# LEDs.net
KiCad netlist of a schematic drawn in Altium Designer
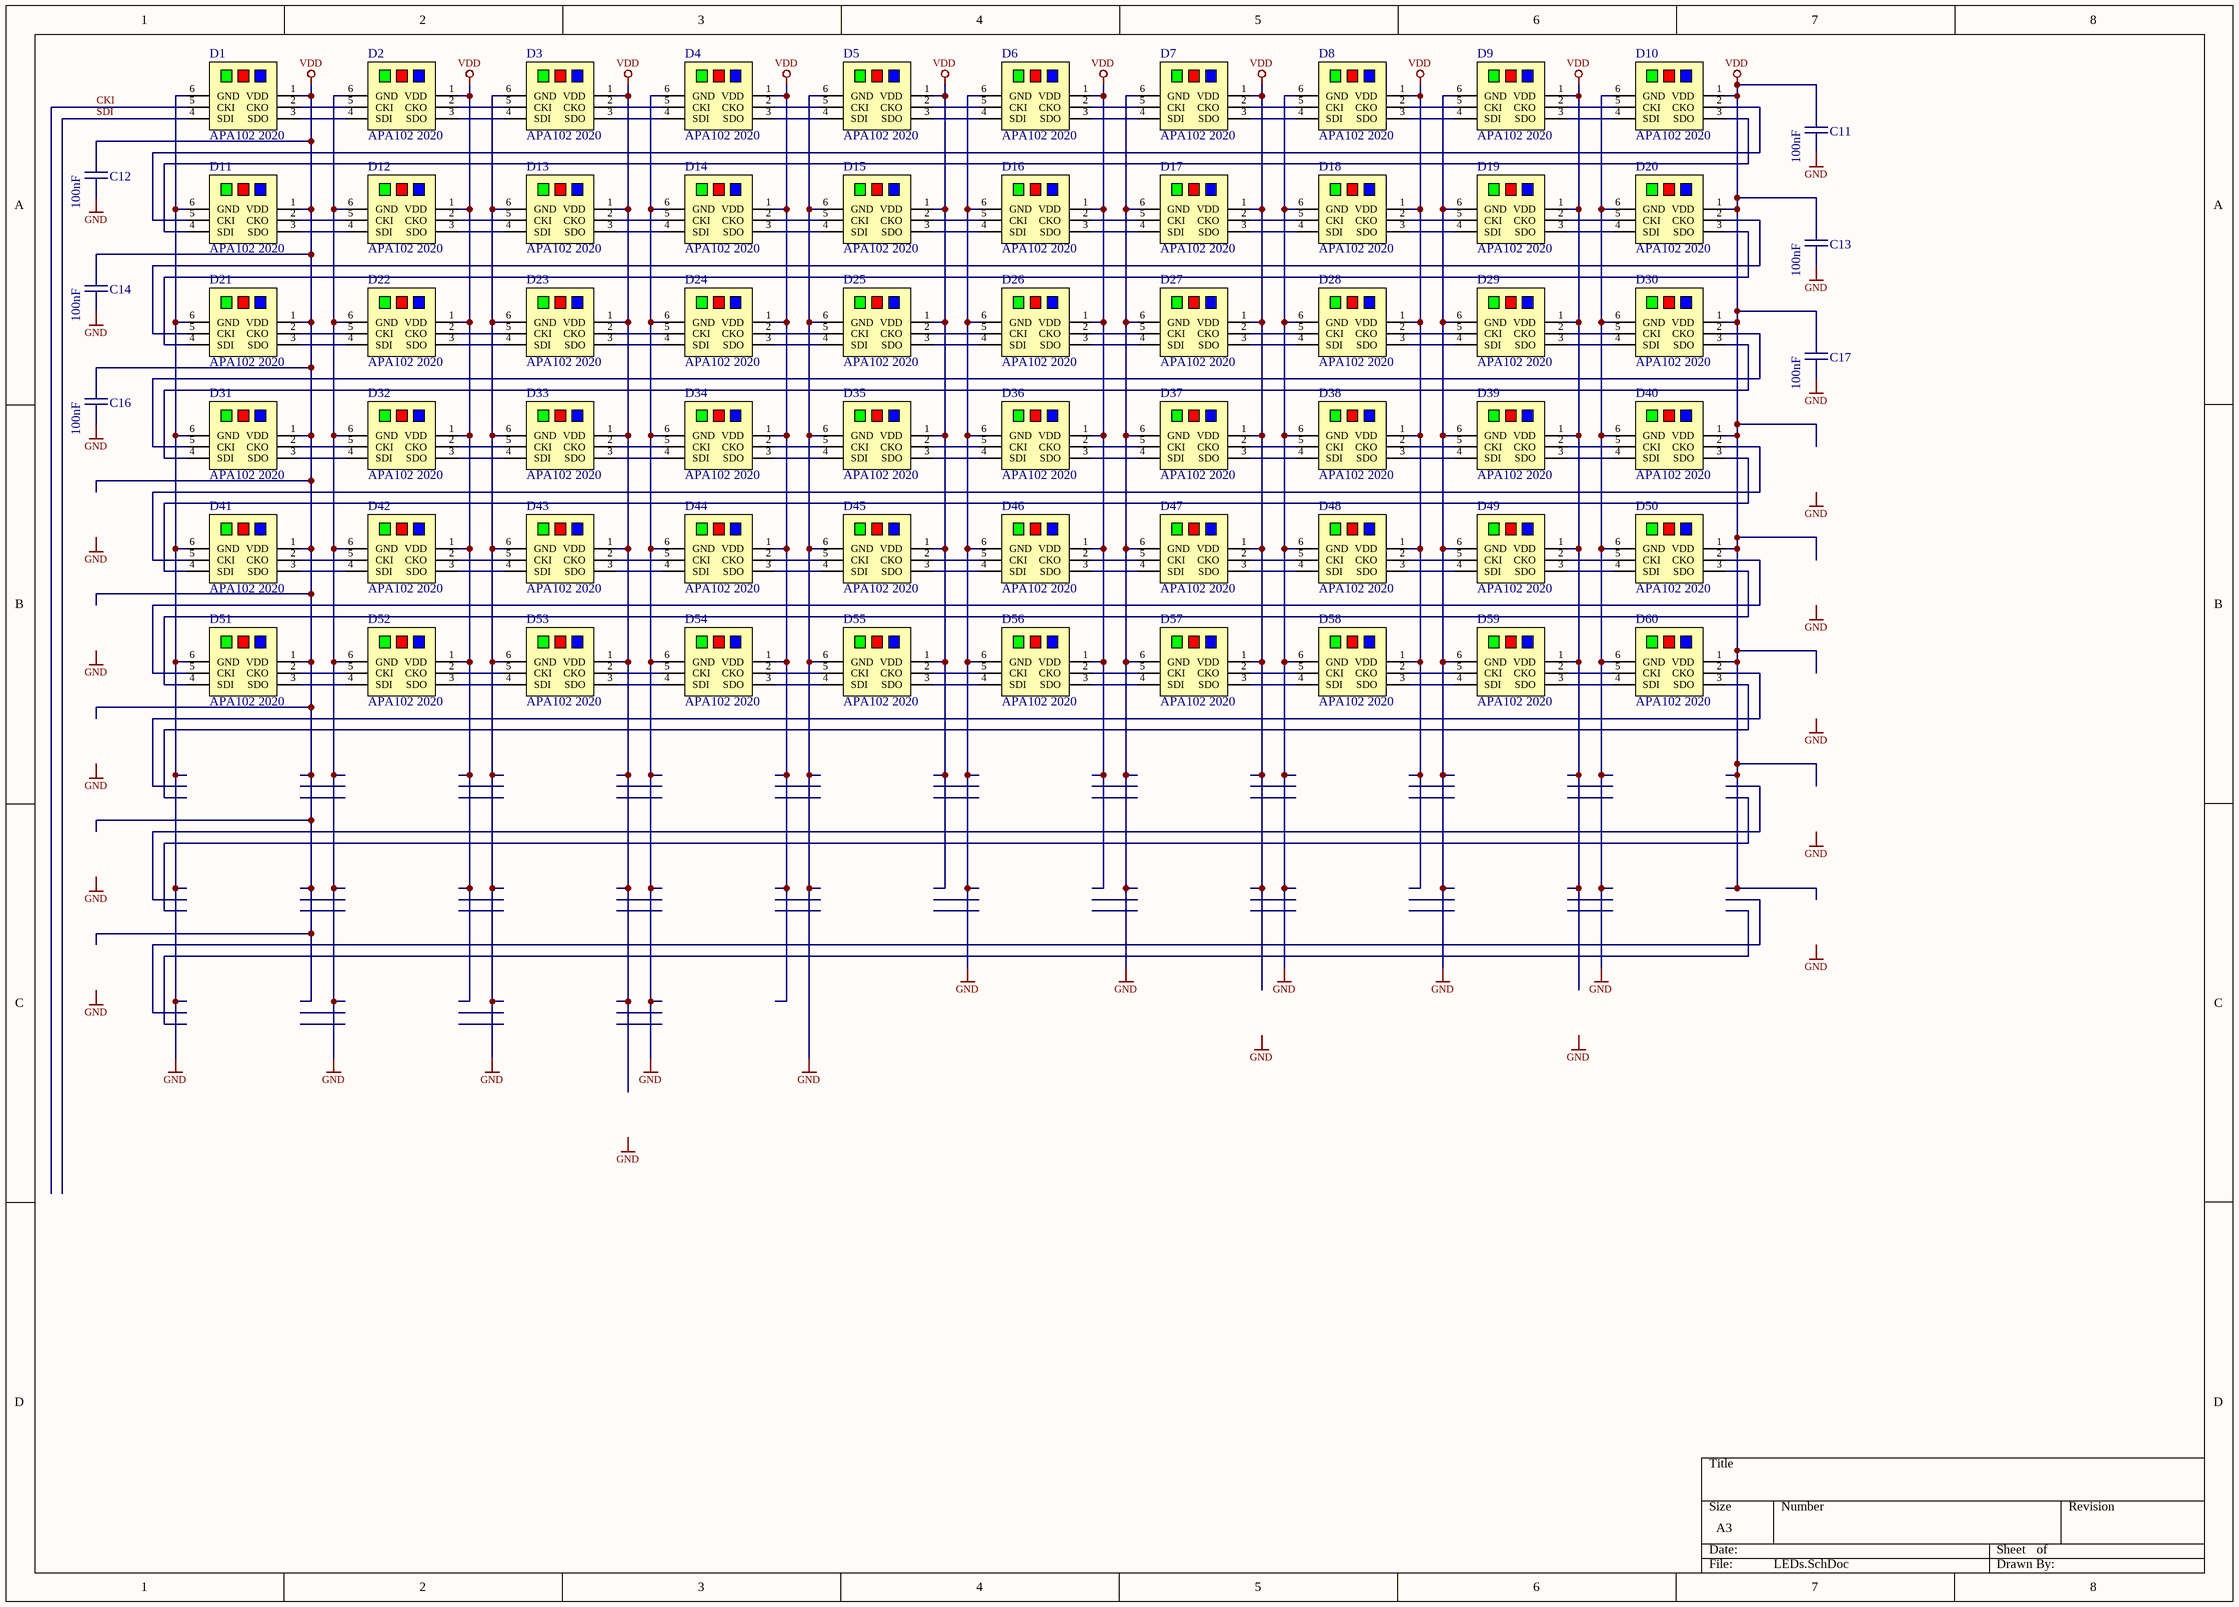
[diagram p0: LEDs.SchDoc]

(export (version "E")
  (design (tool "Eeschema 10.0.6"))
  (components
    (comp (ref "C11")
      (value "100nF")
      (footprint "CAPC0603(1608)55_N")
      (libsource (lib "OVLib_64") (part "CAP"))
    )
    (comp (ref "C12")
      (value "100nF")
      (footprint "CAPC0603(1608)55_N")
      (libsource (lib "OVLib_64") (part "CAP"))
    )
    (comp (ref "C13")
      (value "100nF")
      (footprint "CAPC0603(1608)55_N")
      (libsource (lib "OVLib_64") (part "CAP"))
    )
    (comp (ref "C14")
      (value "100nF")
      (footprint "CAPC0603(1608)55_N")
      (libsource (lib "OVLib_64") (part "CAP"))
    )
    (comp (ref "C16")
      (value "100nF")
      (footprint "CAPC0603(1608)55_N")
      (libsource (lib "OVLib_64") (part "CAP"))
    )
    (comp (ref "C17")
      (value "100nF")
      (footprint "CAPC0603(1608)55_N")
      (libsource (lib "OVLib_64") (part "CAP"))
    )
    (comp (ref "D1")
      (value "APA102 2020")
      (footprint "APA_RGB_LED_2020")
      (libsource (lib "OVLib_64") (part "LED_RGB_APA102"))
    )
    (comp (ref "D2")
      (value "APA102 2020")
      (footprint "APA_RGB_LED_2020")
      (libsource (lib "OVLib_64") (part "LED_RGB_APA102"))
    )
    (comp (ref "D3")
      (value "APA102 2020")
      (footprint "APA_RGB_LED_2020")
      (libsource (lib "OVLib_64") (part "LED_RGB_APA102"))
    )
    (comp (ref "D4")
      (value "APA102 2020")
      (footprint "APA_RGB_LED_2020")
      (libsource (lib "OVLib_64") (part "LED_RGB_APA102"))
    )
    (comp (ref "D5")
      (value "APA102 2020")
      (footprint "APA_RGB_LED_2020")
      (libsource (lib "OVLib_64") (part "LED_RGB_APA102"))
    )
    (comp (ref "D6")
      (value "APA102 2020")
      (footprint "APA_RGB_LED_2020")
      (libsource (lib "OVLib_64") (part "LED_RGB_APA102"))
    )
    (comp (ref "D7")
      (value "APA102 2020")
      (footprint "APA_RGB_LED_2020")
      (libsource (lib "OVLib_64") (part "LED_RGB_APA102"))
    )
    (comp (ref "D8")
      (value "APA102 2020")
      (footprint "APA_RGB_LED_2020")
      (libsource (lib "OVLib_64") (part "LED_RGB_APA102"))
    )
    (comp (ref "D9")
      (value "APA102 2020")
      (footprint "APA_RGB_LED_2020")
      (libsource (lib "OVLib_64") (part "LED_RGB_APA102"))
    )
    (comp (ref "D10")
      (value "APA102 2020")
      (footprint "APA_RGB_LED_2020")
      (libsource (lib "OVLib_64") (part "LED_RGB_APA102"))
    )
    (comp (ref "D11")
      (value "APA102 2020")
      (footprint "APA_RGB_LED_2020")
      (libsource (lib "OVLib_64") (part "LED_RGB_APA102"))
    )
    (comp (ref "D12")
      (value "APA102 2020")
      (footprint "APA_RGB_LED_2020")
      (libsource (lib "OVLib_64") (part "LED_RGB_APA102"))
    )
    (comp (ref "D13")
      (value "APA102 2020")
      (footprint "APA_RGB_LED_2020")
      (libsource (lib "OVLib_64") (part "LED_RGB_APA102"))
    )
    (comp (ref "D14")
      (value "APA102 2020")
      (footprint "APA_RGB_LED_2020")
      (libsource (lib "OVLib_64") (part "LED_RGB_APA102"))
    )
    (comp (ref "D15")
      (value "APA102 2020")
      (footprint "APA_RGB_LED_2020")
      (libsource (lib "OVLib_64") (part "LED_RGB_APA102"))
    )
    (comp (ref "D16")
      (value "APA102 2020")
      (footprint "APA_RGB_LED_2020")
      (libsource (lib "OVLib_64") (part "LED_RGB_APA102"))
    )
    (comp (ref "D17")
      (value "APA102 2020")
      (footprint "APA_RGB_LED_2020")
      (libsource (lib "OVLib_64") (part "LED_RGB_APA102"))
    )
    (comp (ref "D18")
      (value "APA102 2020")
      (footprint "APA_RGB_LED_2020")
      (libsource (lib "OVLib_64") (part "LED_RGB_APA102"))
    )
    (comp (ref "D19")
      (value "APA102 2020")
      (footprint "APA_RGB_LED_2020")
      (libsource (lib "OVLib_64") (part "LED_RGB_APA102"))
    )
    (comp (ref "D20")
      (value "APA102 2020")
      (footprint "APA_RGB_LED_2020")
      (libsource (lib "OVLib_64") (part "LED_RGB_APA102"))
    )
    (comp (ref "D21")
      (value "APA102 2020")
      (footprint "APA_RGB_LED_2020")
      (libsource (lib "OVLib_64") (part "LED_RGB_APA102"))
    )
    (comp (ref "D22")
      (value "APA102 2020")
      (footprint "APA_RGB_LED_2020")
      (libsource (lib "OVLib_64") (part "LED_RGB_APA102"))
    )
    (comp (ref "D23")
      (value "APA102 2020")
      (footprint "APA_RGB_LED_2020")
      (libsource (lib "OVLib_64") (part "LED_RGB_APA102"))
    )
    (comp (ref "D24")
      (value "APA102 2020")
      (footprint "APA_RGB_LED_2020")
      (libsource (lib "OVLib_64") (part "LED_RGB_APA102"))
    )
    (comp (ref "D25")
      (value "APA102 2020")
      (footprint "APA_RGB_LED_2020")
      (libsource (lib "OVLib_64") (part "LED_RGB_APA102"))
    )
    (comp (ref "D26")
      (value "APA102 2020")
      (footprint "APA_RGB_LED_2020")
      (libsource (lib "OVLib_64") (part "LED_RGB_APA102"))
    )
    (comp (ref "D27")
      (value "APA102 2020")
      (footprint "APA_RGB_LED_2020")
      (libsource (lib "OVLib_64") (part "LED_RGB_APA102"))
    )
    (comp (ref "D28")
      (value "APA102 2020")
      (footprint "APA_RGB_LED_2020")
      (libsource (lib "OVLib_64") (part "LED_RGB_APA102"))
    )
    (comp (ref "D29")
      (value "APA102 2020")
      (footprint "APA_RGB_LED_2020")
      (libsource (lib "OVLib_64") (part "LED_RGB_APA102"))
    )
    (comp (ref "D30")
      (value "APA102 2020")
      (footprint "APA_RGB_LED_2020")
      (libsource (lib "OVLib_64") (part "LED_RGB_APA102"))
    )
    (comp (ref "D31")
      (value "APA102 2020")
      (footprint "APA_RGB_LED_2020")
      (libsource (lib "OVLib_64") (part "LED_RGB_APA102"))
    )
    (comp (ref "D32")
      (value "APA102 2020")
      (footprint "APA_RGB_LED_2020")
      (libsource (lib "OVLib_64") (part "LED_RGB_APA102"))
    )
    (comp (ref "D33")
      (value "APA102 2020")
      (footprint "APA_RGB_LED_2020")
      (libsource (lib "OVLib_64") (part "LED_RGB_APA102"))
    )
    (comp (ref "D34")
      (value "APA102 2020")
      (footprint "APA_RGB_LED_2020")
      (libsource (lib "OVLib_64") (part "LED_RGB_APA102"))
    )
    (comp (ref "D35")
      (value "APA102 2020")
      (footprint "APA_RGB_LED_2020")
      (libsource (lib "OVLib_64") (part "LED_RGB_APA102"))
    )
    (comp (ref "D36")
      (value "APA102 2020")
      (footprint "APA_RGB_LED_2020")
      (libsource (lib "OVLib_64") (part "LED_RGB_APA102"))
    )
    (comp (ref "D37")
      (value "APA102 2020")
      (footprint "APA_RGB_LED_2020")
      (libsource (lib "OVLib_64") (part "LED_RGB_APA102"))
    )
    (comp (ref "D38")
      (value "APA102 2020")
      (footprint "APA_RGB_LED_2020")
      (libsource (lib "OVLib_64") (part "LED_RGB_APA102"))
    )
    (comp (ref "D39")
      (value "APA102 2020")
      (footprint "APA_RGB_LED_2020")
      (libsource (lib "OVLib_64") (part "LED_RGB_APA102"))
    )
    (comp (ref "D40")
      (value "APA102 2020")
      (footprint "APA_RGB_LED_2020")
      (libsource (lib "OVLib_64") (part "LED_RGB_APA102"))
    )
    (comp (ref "D41")
      (value "APA102 2020")
      (footprint "APA_RGB_LED_2020")
      (libsource (lib "OVLib_64") (part "LED_RGB_APA102"))
    )
    (comp (ref "D42")
      (value "APA102 2020")
      (footprint "APA_RGB_LED_2020")
      (libsource (lib "OVLib_64") (part "LED_RGB_APA102"))
    )
    (comp (ref "D43")
      (value "APA102 2020")
      (footprint "APA_RGB_LED_2020")
      (libsource (lib "OVLib_64") (part "LED_RGB_APA102"))
    )
    (comp (ref "D44")
      (value "APA102 2020")
      (footprint "APA_RGB_LED_2020")
      (libsource (lib "OVLib_64") (part "LED_RGB_APA102"))
    )
    (comp (ref "D45")
      (value "APA102 2020")
      (footprint "APA_RGB_LED_2020")
      (libsource (lib "OVLib_64") (part "LED_RGB_APA102"))
    )
    (comp (ref "D46")
      (value "APA102 2020")
      (footprint "APA_RGB_LED_2020")
      (libsource (lib "OVLib_64") (part "LED_RGB_APA102"))
    )
    (comp (ref "D47")
      (value "APA102 2020")
      (footprint "APA_RGB_LED_2020")
      (libsource (lib "OVLib_64") (part "LED_RGB_APA102"))
    )
    (comp (ref "D48")
      (value "APA102 2020")
      (footprint "APA_RGB_LED_2020")
      (libsource (lib "OVLib_64") (part "LED_RGB_APA102"))
    )
    (comp (ref "D49")
      (value "APA102 2020")
      (footprint "APA_RGB_LED_2020")
      (libsource (lib "OVLib_64") (part "LED_RGB_APA102"))
    )
    (comp (ref "D50")
      (value "APA102 2020")
      (footprint "APA_RGB_LED_2020")
      (libsource (lib "OVLib_64") (part "LED_RGB_APA102"))
    )
    (comp (ref "D51")
      (value "APA102 2020")
      (footprint "APA_RGB_LED_2020")
      (libsource (lib "OVLib_64") (part "LED_RGB_APA102"))
    )
    (comp (ref "D52")
      (value "APA102 2020")
      (footprint "APA_RGB_LED_2020")
      (libsource (lib "OVLib_64") (part "LED_RGB_APA102"))
    )
    (comp (ref "D53")
      (value "APA102 2020")
      (footprint "APA_RGB_LED_2020")
      (libsource (lib "OVLib_64") (part "LED_RGB_APA102"))
    )
    (comp (ref "D54")
      (value "APA102 2020")
      (footprint "APA_RGB_LED_2020")
      (libsource (lib "OVLib_64") (part "LED_RGB_APA102"))
    )
    (comp (ref "D55")
      (value "APA102 2020")
      (footprint "APA_RGB_LED_2020")
      (libsource (lib "OVLib_64") (part "LED_RGB_APA102"))
    )
    (comp (ref "D56")
      (value "APA102 2020")
      (footprint "APA_RGB_LED_2020")
      (libsource (lib "OVLib_64") (part "LED_RGB_APA102"))
    )
    (comp (ref "D57")
      (value "APA102 2020")
      (footprint "APA_RGB_LED_2020")
      (libsource (lib "OVLib_64") (part "LED_RGB_APA102"))
    )
    (comp (ref "D58")
      (value "APA102 2020")
      (footprint "APA_RGB_LED_2020")
      (libsource (lib "OVLib_64") (part "LED_RGB_APA102"))
    )
    (comp (ref "D59")
      (value "APA102 2020")
      (footprint "APA_RGB_LED_2020")
      (libsource (lib "OVLib_64") (part "LED_RGB_APA102"))
    )
    (comp (ref "D60")
      (value "APA102 2020")
      (footprint "APA_RGB_LED_2020")
      (libsource (lib "OVLib_64") (part "LED_RGB_APA102"))
    )
  )
  (nets
    (net (code "1") (name "/CKI") (class "Default")
      (node (ref "D1") (pin "5") (pinfunction "CKI_5") (pintype "passive"))
    )
    (net (code "2") (name "/SDI") (class "Default")
      (node (ref "D1") (pin "4") (pinfunction "SDI_4") (pintype "passive"))
    )
    (net (code "3") (name "GND") (class "Default")
      (node (ref "C11") (pin "1") (pinfunction "1_1") (pintype "passive"))
      (node (ref "C12") (pin "1") (pinfunction "1_1") (pintype "passive"))
      (node (ref "C13") (pin "1") (pinfunction "1_1") (pintype "passive"))
      (node (ref "C14") (pin "1") (pinfunction "1_1") (pintype "passive"))
      (node (ref "C16") (pin "1") (pinfunction "1_1") (pintype "passive"))
      (node (ref "C17") (pin "1") (pinfunction "1_1") (pintype "passive"))
      (node (ref "D1") (pin "6") (pinfunction "GND_6") (pintype "passive"))
      (node (ref "D10") (pin "6") (pinfunction "GND_6") (pintype "passive"))
      (node (ref "D11") (pin "6") (pinfunction "GND_6") (pintype "passive"))
      (node (ref "D12") (pin "6") (pinfunction "GND_6") (pintype "passive"))
      (node (ref "D13") (pin "6") (pinfunction "GND_6") (pintype "passive"))
      (node (ref "D14") (pin "6") (pinfunction "GND_6") (pintype "passive"))
      (node (ref "D15") (pin "6") (pinfunction "GND_6") (pintype "passive"))
      (node (ref "D16") (pin "6") (pinfunction "GND_6") (pintype "passive"))
      (node (ref "D17") (pin "6") (pinfunction "GND_6") (pintype "passive"))
      (node (ref "D18") (pin "6") (pinfunction "GND_6") (pintype "passive"))
      (node (ref "D19") (pin "6") (pinfunction "GND_6") (pintype "passive"))
      (node (ref "D2") (pin "6") (pinfunction "GND_6") (pintype "passive"))
      (node (ref "D20") (pin "6") (pinfunction "GND_6") (pintype "passive"))
      (node (ref "D21") (pin "6") (pinfunction "GND_6") (pintype "passive"))
      (node (ref "D22") (pin "6") (pinfunction "GND_6") (pintype "passive"))
      (node (ref "D23") (pin "6") (pinfunction "GND_6") (pintype "passive"))
      (node (ref "D24") (pin "6") (pinfunction "GND_6") (pintype "passive"))
      (node (ref "D25") (pin "6") (pinfunction "GND_6") (pintype "passive"))
      (node (ref "D26") (pin "6") (pinfunction "GND_6") (pintype "passive"))
      (node (ref "D27") (pin "6") (pinfunction "GND_6") (pintype "passive"))
      (node (ref "D28") (pin "6") (pinfunction "GND_6") (pintype "passive"))
      (node (ref "D29") (pin "6") (pinfunction "GND_6") (pintype "passive"))
      (node (ref "D3") (pin "6") (pinfunction "GND_6") (pintype "passive"))
      (node (ref "D30") (pin "6") (pinfunction "GND_6") (pintype "passive"))
      (node (ref "D31") (pin "6") (pinfunction "GND_6") (pintype "passive"))
      (node (ref "D32") (pin "6") (pinfunction "GND_6") (pintype "passive"))
      (node (ref "D33") (pin "6") (pinfunction "GND_6") (pintype "passive"))
      (node (ref "D34") (pin "6") (pinfunction "GND_6") (pintype "passive"))
      (node (ref "D35") (pin "6") (pinfunction "GND_6") (pintype "passive"))
      (node (ref "D36") (pin "6") (pinfunction "GND_6") (pintype "passive"))
      (node (ref "D37") (pin "6") (pinfunction "GND_6") (pintype "passive"))
      (node (ref "D38") (pin "6") (pinfunction "GND_6") (pintype "passive"))
      (node (ref "D39") (pin "6") (pinfunction "GND_6") (pintype "passive"))
      (node (ref "D4") (pin "6") (pinfunction "GND_6") (pintype "passive"))
      (node (ref "D40") (pin "6") (pinfunction "GND_6") (pintype "passive"))
      (node (ref "D41") (pin "6") (pinfunction "GND_6") (pintype "passive"))
      (node (ref "D42") (pin "6") (pinfunction "GND_6") (pintype "passive"))
      (node (ref "D43") (pin "6") (pinfunction "GND_6") (pintype "passive"))
      (node (ref "D44") (pin "6") (pinfunction "GND_6") (pintype "passive"))
      (node (ref "D45") (pin "6") (pinfunction "GND_6") (pintype "passive"))
      (node (ref "D46") (pin "6") (pinfunction "GND_6") (pintype "passive"))
      (node (ref "D47") (pin "6") (pinfunction "GND_6") (pintype "passive"))
      (node (ref "D48") (pin "6") (pinfunction "GND_6") (pintype "passive"))
      (node (ref "D49") (pin "6") (pinfunction "GND_6") (pintype "passive"))
      (node (ref "D5") (pin "6") (pinfunction "GND_6") (pintype "passive"))
      (node (ref "D50") (pin "6") (pinfunction "GND_6") (pintype "passive"))
      (node (ref "D51") (pin "6") (pinfunction "GND_6") (pintype "passive"))
      (node (ref "D52") (pin "6") (pinfunction "GND_6") (pintype "passive"))
      (node (ref "D53") (pin "6") (pinfunction "GND_6") (pintype "passive"))
      (node (ref "D54") (pin "6") (pinfunction "GND_6") (pintype "passive"))
      (node (ref "D55") (pin "6") (pinfunction "GND_6") (pintype "passive"))
      (node (ref "D56") (pin "6") (pinfunction "GND_6") (pintype "passive"))
      (node (ref "D57") (pin "6") (pinfunction "GND_6") (pintype "passive"))
      (node (ref "D58") (pin "6") (pinfunction "GND_6") (pintype "passive"))
      (node (ref "D59") (pin "6") (pinfunction "GND_6") (pintype "passive"))
      (node (ref "D6") (pin "6") (pinfunction "GND_6") (pintype "passive"))
      (node (ref "D60") (pin "6") (pinfunction "GND_6") (pintype "passive"))
      (node (ref "D7") (pin "6") (pinfunction "GND_6") (pintype "passive"))
      (node (ref "D8") (pin "6") (pinfunction "GND_6") (pintype "passive"))
      (node (ref "D9") (pin "6") (pinfunction "GND_6") (pintype "passive"))
    )
    (net (code "4") (name "Net-(D1-CKO)") (class "Default")
      (node (ref "D1") (pin "2") (pinfunction "CKO_2") (pintype "passive"))
      (node (ref "D2") (pin "5") (pinfunction "CKI_5") (pintype "passive"))
    )
    (net (code "5") (name "Net-(D1-SDO)") (class "Default")
      (node (ref "D1") (pin "3") (pinfunction "SDO_3") (pintype "passive"))
      (node (ref "D2") (pin "4") (pinfunction "SDI_4") (pintype "passive"))
    )
    (net (code "6") (name "Net-(D2-CKO)") (class "Default")
      (node (ref "D2") (pin "2") (pinfunction "CKO_2") (pintype "passive"))
      (node (ref "D3") (pin "5") (pinfunction "CKI_5") (pintype "passive"))
    )
    (net (code "7") (name "Net-(D2-SDO)") (class "Default")
      (node (ref "D2") (pin "3") (pinfunction "SDO_3") (pintype "passive"))
      (node (ref "D3") (pin "4") (pinfunction "SDI_4") (pintype "passive"))
    )
    (net (code "8") (name "Net-(D3-CKO)") (class "Default")
      (node (ref "D3") (pin "2") (pinfunction "CKO_2") (pintype "passive"))
      (node (ref "D4") (pin "5") (pinfunction "CKI_5") (pintype "passive"))
    )
    (net (code "9") (name "Net-(D3-SDO)") (class "Default")
      (node (ref "D3") (pin "3") (pinfunction "SDO_3") (pintype "passive"))
      (node (ref "D4") (pin "4") (pinfunction "SDI_4") (pintype "passive"))
    )
    (net (code "10") (name "Net-(D4-CKO)") (class "Default")
      (node (ref "D4") (pin "2") (pinfunction "CKO_2") (pintype "passive"))
      (node (ref "D5") (pin "5") (pinfunction "CKI_5") (pintype "passive"))
    )
    (net (code "11") (name "Net-(D4-SDO)") (class "Default")
      (node (ref "D4") (pin "3") (pinfunction "SDO_3") (pintype "passive"))
      (node (ref "D5") (pin "4") (pinfunction "SDI_4") (pintype "passive"))
    )
    (net (code "12") (name "Net-(D5-CKO)") (class "Default")
      (node (ref "D5") (pin "2") (pinfunction "CKO_2") (pintype "passive"))
      (node (ref "D6") (pin "5") (pinfunction "CKI_5") (pintype "passive"))
    )
    (net (code "13") (name "Net-(D5-SDO)") (class "Default")
      (node (ref "D5") (pin "3") (pinfunction "SDO_3") (pintype "passive"))
      (node (ref "D6") (pin "4") (pinfunction "SDI_4") (pintype "passive"))
    )
    (net (code "14") (name "Net-(D6-CKO)") (class "Default")
      (node (ref "D6") (pin "2") (pinfunction "CKO_2") (pintype "passive"))
      (node (ref "D7") (pin "5") (pinfunction "CKI_5") (pintype "passive"))
    )
    (net (code "15") (name "Net-(D6-SDO)") (class "Default")
      (node (ref "D6") (pin "3") (pinfunction "SDO_3") (pintype "passive"))
      (node (ref "D7") (pin "4") (pinfunction "SDI_4") (pintype "passive"))
    )
    (net (code "16") (name "Net-(D7-CKO)") (class "Default")
      (node (ref "D7") (pin "2") (pinfunction "CKO_2") (pintype "passive"))
      (node (ref "D8") (pin "5") (pinfunction "CKI_5") (pintype "passive"))
    )
    (net (code "17") (name "Net-(D7-SDO)") (class "Default")
      (node (ref "D7") (pin "3") (pinfunction "SDO_3") (pintype "passive"))
      (node (ref "D8") (pin "4") (pinfunction "SDI_4") (pintype "passive"))
    )
    (net (code "18") (name "Net-(D8-CKO)") (class "Default")
      (node (ref "D8") (pin "2") (pinfunction "CKO_2") (pintype "passive"))
      (node (ref "D9") (pin "5") (pinfunction "CKI_5") (pintype "passive"))
    )
    (net (code "19") (name "Net-(D8-SDO)") (class "Default")
      (node (ref "D8") (pin "3") (pinfunction "SDO_3") (pintype "passive"))
      (node (ref "D9") (pin "4") (pinfunction "SDI_4") (pintype "passive"))
    )
    (net (code "20") (name "Net-(D10-CKI)") (class "Default")
      (node (ref "D10") (pin "5") (pinfunction "CKI_5") (pintype "passive"))
      (node (ref "D9") (pin "2") (pinfunction "CKO_2") (pintype "passive"))
    )
    (net (code "21") (name "Net-(D10-CKO)") (class "Default")
      (node (ref "D10") (pin "2") (pinfunction "CKO_2") (pintype "passive"))
      (node (ref "D11") (pin "5") (pinfunction "CKI_5") (pintype "passive"))
    )
    (net (code "22") (name "Net-(D10-SDI)") (class "Default")
      (node (ref "D10") (pin "4") (pinfunction "SDI_4") (pintype "passive"))
      (node (ref "D9") (pin "3") (pinfunction "SDO_3") (pintype "passive"))
    )
    (net (code "23") (name "Net-(D10-SDO)") (class "Default")
      (node (ref "D10") (pin "3") (pinfunction "SDO_3") (pintype "passive"))
      (node (ref "D11") (pin "4") (pinfunction "SDI_4") (pintype "passive"))
    )
    (net (code "24") (name "Net-(D11-CKO)") (class "Default")
      (node (ref "D11") (pin "2") (pinfunction "CKO_2") (pintype "passive"))
      (node (ref "D12") (pin "5") (pinfunction "CKI_5") (pintype "passive"))
    )
    (net (code "25") (name "Net-(D11-SDO)") (class "Default")
      (node (ref "D11") (pin "3") (pinfunction "SDO_3") (pintype "passive"))
      (node (ref "D12") (pin "4") (pinfunction "SDI_4") (pintype "passive"))
    )
    (net (code "26") (name "Net-(D12-CKO)") (class "Default")
      (node (ref "D12") (pin "2") (pinfunction "CKO_2") (pintype "passive"))
      (node (ref "D13") (pin "5") (pinfunction "CKI_5") (pintype "passive"))
    )
    (net (code "27") (name "Net-(D12-SDO)") (class "Default")
      (node (ref "D12") (pin "3") (pinfunction "SDO_3") (pintype "passive"))
      (node (ref "D13") (pin "4") (pinfunction "SDI_4") (pintype "passive"))
    )
    (net (code "28") (name "Net-(D13-CKO)") (class "Default")
      (node (ref "D13") (pin "2") (pinfunction "CKO_2") (pintype "passive"))
      (node (ref "D14") (pin "5") (pinfunction "CKI_5") (pintype "passive"))
    )
    (net (code "29") (name "Net-(D13-SDO)") (class "Default")
      (node (ref "D13") (pin "3") (pinfunction "SDO_3") (pintype "passive"))
      (node (ref "D14") (pin "4") (pinfunction "SDI_4") (pintype "passive"))
    )
    (net (code "30") (name "Net-(D14-CKO)") (class "Default")
      (node (ref "D14") (pin "2") (pinfunction "CKO_2") (pintype "passive"))
      (node (ref "D15") (pin "5") (pinfunction "CKI_5") (pintype "passive"))
    )
    (net (code "31") (name "Net-(D14-SDO)") (class "Default")
      (node (ref "D14") (pin "3") (pinfunction "SDO_3") (pintype "passive"))
      (node (ref "D15") (pin "4") (pinfunction "SDI_4") (pintype "passive"))
    )
    (net (code "32") (name "Net-(D15-CKO)") (class "Default")
      (node (ref "D15") (pin "2") (pinfunction "CKO_2") (pintype "passive"))
      (node (ref "D16") (pin "5") (pinfunction "CKI_5") (pintype "passive"))
    )
    (net (code "33") (name "Net-(D15-SDO)") (class "Default")
      (node (ref "D15") (pin "3") (pinfunction "SDO_3") (pintype "passive"))
      (node (ref "D16") (pin "4") (pinfunction "SDI_4") (pintype "passive"))
    )
    (net (code "34") (name "Net-(D16-CKO)") (class "Default")
      (node (ref "D16") (pin "2") (pinfunction "CKO_2") (pintype "passive"))
      (node (ref "D17") (pin "5") (pinfunction "CKI_5") (pintype "passive"))
    )
    (net (code "35") (name "Net-(D16-SDO)") (class "Default")
      (node (ref "D16") (pin "3") (pinfunction "SDO_3") (pintype "passive"))
      (node (ref "D17") (pin "4") (pinfunction "SDI_4") (pintype "passive"))
    )
    (net (code "36") (name "Net-(D17-CKO)") (class "Default")
      (node (ref "D17") (pin "2") (pinfunction "CKO_2") (pintype "passive"))
      (node (ref "D18") (pin "5") (pinfunction "CKI_5") (pintype "passive"))
    )
    (net (code "37") (name "Net-(D17-SDO)") (class "Default")
      (node (ref "D17") (pin "3") (pinfunction "SDO_3") (pintype "passive"))
      (node (ref "D18") (pin "4") (pinfunction "SDI_4") (pintype "passive"))
    )
    (net (code "38") (name "Net-(D18-CKO)") (class "Default")
      (node (ref "D18") (pin "2") (pinfunction "CKO_2") (pintype "passive"))
      (node (ref "D19") (pin "5") (pinfunction "CKI_5") (pintype "passive"))
    )
    (net (code "39") (name "Net-(D18-SDO)") (class "Default")
      (node (ref "D18") (pin "3") (pinfunction "SDO_3") (pintype "passive"))
      (node (ref "D19") (pin "4") (pinfunction "SDI_4") (pintype "passive"))
    )
    (net (code "40") (name "Net-(D19-CKO)") (class "Default")
      (node (ref "D19") (pin "2") (pinfunction "CKO_2") (pintype "passive"))
      (node (ref "D20") (pin "5") (pinfunction "CKI_5") (pintype "passive"))
    )
    (net (code "41") (name "Net-(D19-SDO)") (class "Default")
      (node (ref "D19") (pin "3") (pinfunction "SDO_3") (pintype "passive"))
      (node (ref "D20") (pin "4") (pinfunction "SDI_4") (pintype "passive"))
    )
    (net (code "42") (name "Net-(D20-CKO)") (class "Default")
      (node (ref "D20") (pin "2") (pinfunction "CKO_2") (pintype "passive"))
      (node (ref "D21") (pin "5") (pinfunction "CKI_5") (pintype "passive"))
    )
    (net (code "43") (name "Net-(D20-SDO)") (class "Default")
      (node (ref "D20") (pin "3") (pinfunction "SDO_3") (pintype "passive"))
      (node (ref "D21") (pin "4") (pinfunction "SDI_4") (pintype "passive"))
    )
    (net (code "44") (name "Net-(D21-CKO)") (class "Default")
      (node (ref "D21") (pin "2") (pinfunction "CKO_2") (pintype "passive"))
      (node (ref "D22") (pin "5") (pinfunction "CKI_5") (pintype "passive"))
    )
    (net (code "45") (name "Net-(D21-SDO)") (class "Default")
      (node (ref "D21") (pin "3") (pinfunction "SDO_3") (pintype "passive"))
      (node (ref "D22") (pin "4") (pinfunction "SDI_4") (pintype "passive"))
    )
    (net (code "46") (name "Net-(D22-CKO)") (class "Default")
      (node (ref "D22") (pin "2") (pinfunction "CKO_2") (pintype "passive"))
      (node (ref "D23") (pin "5") (pinfunction "CKI_5") (pintype "passive"))
    )
    (net (code "47") (name "Net-(D22-SDO)") (class "Default")
      (node (ref "D22") (pin "3") (pinfunction "SDO_3") (pintype "passive"))
      (node (ref "D23") (pin "4") (pinfunction "SDI_4") (pintype "passive"))
    )
    (net (code "48") (name "Net-(D23-CKO)") (class "Default")
      (node (ref "D23") (pin "2") (pinfunction "CKO_2") (pintype "passive"))
      (node (ref "D24") (pin "5") (pinfunction "CKI_5") (pintype "passive"))
    )
    (net (code "49") (name "Net-(D23-SDO)") (class "Default")
      (node (ref "D23") (pin "3") (pinfunction "SDO_3") (pintype "passive"))
      (node (ref "D24") (pin "4") (pinfunction "SDI_4") (pintype "passive"))
    )
    (net (code "50") (name "Net-(D24-CKO)") (class "Default")
      (node (ref "D24") (pin "2") (pinfunction "CKO_2") (pintype "passive"))
      (node (ref "D25") (pin "5") (pinfunction "CKI_5") (pintype "passive"))
    )
    (net (code "51") (name "Net-(D24-SDO)") (class "Default")
      (node (ref "D24") (pin "3") (pinfunction "SDO_3") (pintype "passive"))
      (node (ref "D25") (pin "4") (pinfunction "SDI_4") (pintype "passive"))
    )
    (net (code "52") (name "Net-(D25-CKO)") (class "Default")
      (node (ref "D25") (pin "2") (pinfunction "CKO_2") (pintype "passive"))
      (node (ref "D26") (pin "5") (pinfunction "CKI_5") (pintype "passive"))
    )
    (net (code "53") (name "Net-(D25-SDO)") (class "Default")
      (node (ref "D25") (pin "3") (pinfunction "SDO_3") (pintype "passive"))
      (node (ref "D26") (pin "4") (pinfunction "SDI_4") (pintype "passive"))
    )
    (net (code "54") (name "Net-(D26-CKO)") (class "Default")
      (node (ref "D26") (pin "2") (pinfunction "CKO_2") (pintype "passive"))
      (node (ref "D27") (pin "5") (pinfunction "CKI_5") (pintype "passive"))
    )
    (net (code "55") (name "Net-(D26-SDO)") (class "Default")
      (node (ref "D26") (pin "3") (pinfunction "SDO_3") (pintype "passive"))
      (node (ref "D27") (pin "4") (pinfunction "SDI_4") (pintype "passive"))
    )
    (net (code "56") (name "Net-(D27-CKO)") (class "Default")
      (node (ref "D27") (pin "2") (pinfunction "CKO_2") (pintype "passive"))
      (node (ref "D28") (pin "5") (pinfunction "CKI_5") (pintype "passive"))
    )
    (net (code "57") (name "Net-(D27-SDO)") (class "Default")
      (node (ref "D27") (pin "3") (pinfunction "SDO_3") (pintype "passive"))
      (node (ref "D28") (pin "4") (pinfunction "SDI_4") (pintype "passive"))
    )
    (net (code "58") (name "Net-(D28-CKO)") (class "Default")
      (node (ref "D28") (pin "2") (pinfunction "CKO_2") (pintype "passive"))
      (node (ref "D29") (pin "5") (pinfunction "CKI_5") (pintype "passive"))
    )
    (net (code "59") (name "Net-(D28-SDO)") (class "Default")
      (node (ref "D28") (pin "3") (pinfunction "SDO_3") (pintype "passive"))
      (node (ref "D29") (pin "4") (pinfunction "SDI_4") (pintype "passive"))
    )
    (net (code "60") (name "Net-(D29-CKO)") (class "Default")
      (node (ref "D29") (pin "2") (pinfunction "CKO_2") (pintype "passive"))
      (node (ref "D30") (pin "5") (pinfunction "CKI_5") (pintype "passive"))
    )
    (net (code "61") (name "Net-(D29-SDO)") (class "Default")
      (node (ref "D29") (pin "3") (pinfunction "SDO_3") (pintype "passive"))
      (node (ref "D30") (pin "4") (pinfunction "SDI_4") (pintype "passive"))
    )
    (net (code "62") (name "Net-(D30-CKO)") (class "Default")
      (node (ref "D30") (pin "2") (pinfunction "CKO_2") (pintype "passive"))
      (node (ref "D31") (pin "5") (pinfunction "CKI_5") (pintype "passive"))
    )
    (net (code "63") (name "Net-(D30-SDO)") (class "Default")
      (node (ref "D30") (pin "3") (pinfunction "SDO_3") (pintype "passive"))
      (node (ref "D31") (pin "4") (pinfunction "SDI_4") (pintype "passive"))
    )
    (net (code "64") (name "Net-(D31-CKO)") (class "Default")
      (node (ref "D31") (pin "2") (pinfunction "CKO_2") (pintype "passive"))
      (node (ref "D32") (pin "5") (pinfunction "CKI_5") (pintype "passive"))
    )
    (net (code "65") (name "Net-(D31-SDO)") (class "Default")
      (node (ref "D31") (pin "3") (pinfunction "SDO_3") (pintype "passive"))
      (node (ref "D32") (pin "4") (pinfunction "SDI_4") (pintype "passive"))
    )
    (net (code "66") (name "Net-(D32-CKO)") (class "Default")
      (node (ref "D32") (pin "2") (pinfunction "CKO_2") (pintype "passive"))
      (node (ref "D33") (pin "5") (pinfunction "CKI_5") (pintype "passive"))
    )
    (net (code "67") (name "Net-(D32-SDO)") (class "Default")
      (node (ref "D32") (pin "3") (pinfunction "SDO_3") (pintype "passive"))
      (node (ref "D33") (pin "4") (pinfunction "SDI_4") (pintype "passive"))
    )
    (net (code "68") (name "Net-(D33-CKO)") (class "Default")
      (node (ref "D33") (pin "2") (pinfunction "CKO_2") (pintype "passive"))
      (node (ref "D34") (pin "5") (pinfunction "CKI_5") (pintype "passive"))
    )
    (net (code "69") (name "Net-(D33-SDO)") (class "Default")
      (node (ref "D33") (pin "3") (pinfunction "SDO_3") (pintype "passive"))
      (node (ref "D34") (pin "4") (pinfunction "SDI_4") (pintype "passive"))
    )
    (net (code "70") (name "Net-(D34-CKO)") (class "Default")
      (node (ref "D34") (pin "2") (pinfunction "CKO_2") (pintype "passive"))
      (node (ref "D35") (pin "5") (pinfunction "CKI_5") (pintype "passive"))
    )
    (net (code "71") (name "Net-(D34-SDO)") (class "Default")
      (node (ref "D34") (pin "3") (pinfunction "SDO_3") (pintype "passive"))
      (node (ref "D35") (pin "4") (pinfunction "SDI_4") (pintype "passive"))
    )
    (net (code "72") (name "Net-(D35-CKO)") (class "Default")
      (node (ref "D35") (pin "2") (pinfunction "CKO_2") (pintype "passive"))
      (node (ref "D36") (pin "5") (pinfunction "CKI_5") (pintype "passive"))
    )
    (net (code "73") (name "Net-(D35-SDO)") (class "Default")
      (node (ref "D35") (pin "3") (pinfunction "SDO_3") (pintype "passive"))
      (node (ref "D36") (pin "4") (pinfunction "SDI_4") (pintype "passive"))
    )
    (net (code "74") (name "Net-(D36-CKO)") (class "Default")
      (node (ref "D36") (pin "2") (pinfunction "CKO_2") (pintype "passive"))
      (node (ref "D37") (pin "5") (pinfunction "CKI_5") (pintype "passive"))
    )
    (net (code "75") (name "Net-(D36-SDO)") (class "Default")
      (node (ref "D36") (pin "3") (pinfunction "SDO_3") (pintype "passive"))
      (node (ref "D37") (pin "4") (pinfunction "SDI_4") (pintype "passive"))
    )
    (net (code "76") (name "Net-(D37-CKO)") (class "Default")
      (node (ref "D37") (pin "2") (pinfunction "CKO_2") (pintype "passive"))
      (node (ref "D38") (pin "5") (pinfunction "CKI_5") (pintype "passive"))
    )
    (net (code "77") (name "Net-(D37-SDO)") (class "Default")
      (node (ref "D37") (pin "3") (pinfunction "SDO_3") (pintype "passive"))
      (node (ref "D38") (pin "4") (pinfunction "SDI_4") (pintype "passive"))
    )
    (net (code "78") (name "Net-(D38-CKO)") (class "Default")
      (node (ref "D38") (pin "2") (pinfunction "CKO_2") (pintype "passive"))
      (node (ref "D39") (pin "5") (pinfunction "CKI_5") (pintype "passive"))
    )
    (net (code "79") (name "Net-(D38-SDO)") (class "Default")
      (node (ref "D38") (pin "3") (pinfunction "SDO_3") (pintype "passive"))
      (node (ref "D39") (pin "4") (pinfunction "SDI_4") (pintype "passive"))
    )
    (net (code "80") (name "Net-(D39-CKO)") (class "Default")
      (node (ref "D39") (pin "2") (pinfunction "CKO_2") (pintype "passive"))
      (node (ref "D40") (pin "5") (pinfunction "CKI_5") (pintype "passive"))
    )
    (net (code "81") (name "Net-(D39-SDO)") (class "Default")
      (node (ref "D39") (pin "3") (pinfunction "SDO_3") (pintype "passive"))
      (node (ref "D40") (pin "4") (pinfunction "SDI_4") (pintype "passive"))
    )
    (net (code "82") (name "Net-(D40-CKO)") (class "Default")
      (node (ref "D40") (pin "2") (pinfunction "CKO_2") (pintype "passive"))
      (node (ref "D41") (pin "5") (pinfunction "CKI_5") (pintype "passive"))
    )
    (net (code "83") (name "Net-(D40-SDO)") (class "Default")
      (node (ref "D40") (pin "3") (pinfunction "SDO_3") (pintype "passive"))
      (node (ref "D41") (pin "4") (pinfunction "SDI_4") (pintype "passive"))
    )
    (net (code "84") (name "Net-(D41-CKO)") (class "Default")
      (node (ref "D41") (pin "2") (pinfunction "CKO_2") (pintype "passive"))
      (node (ref "D42") (pin "5") (pinfunction "CKI_5") (pintype "passive"))
    )
    (net (code "85") (name "Net-(D41-SDO)") (class "Default")
      (node (ref "D41") (pin "3") (pinfunction "SDO_3") (pintype "passive"))
      (node (ref "D42") (pin "4") (pinfunction "SDI_4") (pintype "passive"))
    )
    (net (code "86") (name "Net-(D42-CKO)") (class "Default")
      (node (ref "D42") (pin "2") (pinfunction "CKO_2") (pintype "passive"))
      (node (ref "D43") (pin "5") (pinfunction "CKI_5") (pintype "passive"))
    )
    (net (code "87") (name "Net-(D42-SDO)") (class "Default")
      (node (ref "D42") (pin "3") (pinfunction "SDO_3") (pintype "passive"))
      (node (ref "D43") (pin "4") (pinfunction "SDI_4") (pintype "passive"))
    )
    (net (code "88") (name "Net-(D43-CKO)") (class "Default")
      (node (ref "D43") (pin "2") (pinfunction "CKO_2") (pintype "passive"))
      (node (ref "D44") (pin "5") (pinfunction "CKI_5") (pintype "passive"))
    )
    (net (code "89") (name "Net-(D43-SDO)") (class "Default")
      (node (ref "D43") (pin "3") (pinfunction "SDO_3") (pintype "passive"))
      (node (ref "D44") (pin "4") (pinfunction "SDI_4") (pintype "passive"))
    )
    (net (code "90") (name "Net-(D44-CKO)") (class "Default")
      (node (ref "D44") (pin "2") (pinfunction "CKO_2") (pintype "passive"))
      (node (ref "D45") (pin "5") (pinfunction "CKI_5") (pintype "passive"))
    )
    (net (code "91") (name "Net-(D44-SDO)") (class "Default")
      (node (ref "D44") (pin "3") (pinfunction "SDO_3") (pintype "passive"))
      (node (ref "D45") (pin "4") (pinfunction "SDI_4") (pintype "passive"))
    )
    (net (code "92") (name "Net-(D45-CKO)") (class "Default")
      (node (ref "D45") (pin "2") (pinfunction "CKO_2") (pintype "passive"))
      (node (ref "D46") (pin "5") (pinfunction "CKI_5") (pintype "passive"))
    )
    (net (code "93") (name "Net-(D45-SDO)") (class "Default")
      (node (ref "D45") (pin "3") (pinfunction "SDO_3") (pintype "passive"))
      (node (ref "D46") (pin "4") (pinfunction "SDI_4") (pintype "passive"))
    )
    (net (code "94") (name "Net-(D46-CKO)") (class "Default")
      (node (ref "D46") (pin "2") (pinfunction "CKO_2") (pintype "passive"))
      (node (ref "D47") (pin "5") (pinfunction "CKI_5") (pintype "passive"))
    )
    (net (code "95") (name "Net-(D46-SDO)") (class "Default")
      (node (ref "D46") (pin "3") (pinfunction "SDO_3") (pintype "passive"))
      (node (ref "D47") (pin "4") (pinfunction "SDI_4") (pintype "passive"))
    )
    (net (code "96") (name "Net-(D47-CKO)") (class "Default")
      (node (ref "D47") (pin "2") (pinfunction "CKO_2") (pintype "passive"))
      (node (ref "D48") (pin "5") (pinfunction "CKI_5") (pintype "passive"))
    )
    (net (code "97") (name "Net-(D47-SDO)") (class "Default")
      (node (ref "D47") (pin "3") (pinfunction "SDO_3") (pintype "passive"))
      (node (ref "D48") (pin "4") (pinfunction "SDI_4") (pintype "passive"))
    )
    (net (code "98") (name "Net-(D48-CKO)") (class "Default")
      (node (ref "D48") (pin "2") (pinfunction "CKO_2") (pintype "passive"))
      (node (ref "D49") (pin "5") (pinfunction "CKI_5") (pintype "passive"))
    )
    (net (code "99") (name "Net-(D48-SDO)") (class "Default")
      (node (ref "D48") (pin "3") (pinfunction "SDO_3") (pintype "passive"))
      (node (ref "D49") (pin "4") (pinfunction "SDI_4") (pintype "passive"))
    )
    (net (code "100") (name "Net-(D49-CKO)") (class "Default")
      (node (ref "D49") (pin "2") (pinfunction "CKO_2") (pintype "passive"))
      (node (ref "D50") (pin "5") (pinfunction "CKI_5") (pintype "passive"))
    )
    (net (code "101") (name "Net-(D49-SDO)") (class "Default")
      (node (ref "D49") (pin "3") (pinfunction "SDO_3") (pintype "passive"))
      (node (ref "D50") (pin "4") (pinfunction "SDI_4") (pintype "passive"))
    )
    (net (code "102") (name "Net-(D50-CKO)") (class "Default")
      (node (ref "D50") (pin "2") (pinfunction "CKO_2") (pintype "passive"))
      (node (ref "D51") (pin "5") (pinfunction "CKI_5") (pintype "passive"))
    )
    (net (code "103") (name "Net-(D50-SDO)") (class "Default")
      (node (ref "D50") (pin "3") (pinfunction "SDO_3") (pintype "passive"))
      (node (ref "D51") (pin "4") (pinfunction "SDI_4") (pintype "passive"))
    )
    (net (code "104") (name "Net-(D51-CKO)") (class "Default")
      (node (ref "D51") (pin "2") (pinfunction "CKO_2") (pintype "passive"))
      (node (ref "D52") (pin "5") (pinfunction "CKI_5") (pintype "passive"))
    )
    (net (code "105") (name "Net-(D51-SDO)") (class "Default")
      (node (ref "D51") (pin "3") (pinfunction "SDO_3") (pintype "passive"))
      (node (ref "D52") (pin "4") (pinfunction "SDI_4") (pintype "passive"))
    )
    (net (code "106") (name "Net-(D52-CKO)") (class "Default")
      (node (ref "D52") (pin "2") (pinfunction "CKO_2") (pintype "passive"))
      (node (ref "D53") (pin "5") (pinfunction "CKI_5") (pintype "passive"))
    )
    (net (code "107") (name "Net-(D52-SDO)") (class "Default")
      (node (ref "D52") (pin "3") (pinfunction "SDO_3") (pintype "passive"))
      (node (ref "D53") (pin "4") (pinfunction "SDI_4") (pintype "passive"))
    )
    (net (code "108") (name "Net-(D53-CKO)") (class "Default")
      (node (ref "D53") (pin "2") (pinfunction "CKO_2") (pintype "passive"))
      (node (ref "D54") (pin "5") (pinfunction "CKI_5") (pintype "passive"))
    )
    (net (code "109") (name "Net-(D53-SDO)") (class "Default")
      (node (ref "D53") (pin "3") (pinfunction "SDO_3") (pintype "passive"))
      (node (ref "D54") (pin "4") (pinfunction "SDI_4") (pintype "passive"))
    )
    (net (code "110") (name "Net-(D54-CKO)") (class "Default")
      (node (ref "D54") (pin "2") (pinfunction "CKO_2") (pintype "passive"))
      (node (ref "D55") (pin "5") (pinfunction "CKI_5") (pintype "passive"))
    )
    (net (code "111") (name "Net-(D54-SDO)") (class "Default")
      (node (ref "D54") (pin "3") (pinfunction "SDO_3") (pintype "passive"))
      (node (ref "D55") (pin "4") (pinfunction "SDI_4") (pintype "passive"))
    )
    (net (code "112") (name "Net-(D55-CKO)") (class "Default")
      (node (ref "D55") (pin "2") (pinfunction "CKO_2") (pintype "passive"))
      (node (ref "D56") (pin "5") (pinfunction "CKI_5") (pintype "passive"))
    )
    (net (code "113") (name "Net-(D55-SDO)") (class "Default")
      (node (ref "D55") (pin "3") (pinfunction "SDO_3") (pintype "passive"))
      (node (ref "D56") (pin "4") (pinfunction "SDI_4") (pintype "passive"))
    )
    (net (code "114") (name "Net-(D56-CKO)") (class "Default")
      (node (ref "D56") (pin "2") (pinfunction "CKO_2") (pintype "passive"))
      (node (ref "D57") (pin "5") (pinfunction "CKI_5") (pintype "passive"))
    )
    (net (code "115") (name "Net-(D56-SDO)") (class "Default")
      (node (ref "D56") (pin "3") (pinfunction "SDO_3") (pintype "passive"))
      (node (ref "D57") (pin "4") (pinfunction "SDI_4") (pintype "passive"))
    )
    (net (code "116") (name "Net-(D57-CKO)") (class "Default")
      (node (ref "D57") (pin "2") (pinfunction "CKO_2") (pintype "passive"))
      (node (ref "D58") (pin "5") (pinfunction "CKI_5") (pintype "passive"))
    )
    (net (code "117") (name "Net-(D57-SDO)") (class "Default")
      (node (ref "D57") (pin "3") (pinfunction "SDO_3") (pintype "passive"))
      (node (ref "D58") (pin "4") (pinfunction "SDI_4") (pintype "passive"))
    )
    (net (code "118") (name "Net-(D58-CKO)") (class "Default")
      (node (ref "D58") (pin "2") (pinfunction "CKO_2") (pintype "passive"))
      (node (ref "D59") (pin "5") (pinfunction "CKI_5") (pintype "passive"))
    )
    (net (code "119") (name "Net-(D58-SDO)") (class "Default")
      (node (ref "D58") (pin "3") (pinfunction "SDO_3") (pintype "passive"))
      (node (ref "D59") (pin "4") (pinfunction "SDI_4") (pintype "passive"))
    )
    (net (code "120") (name "Net-(D59-CKO)") (class "Default")
      (node (ref "D59") (pin "2") (pinfunction "CKO_2") (pintype "passive"))
      (node (ref "D60") (pin "5") (pinfunction "CKI_5") (pintype "passive"))
    )
    (net (code "121") (name "Net-(D59-SDO)") (class "Default")
      (node (ref "D59") (pin "3") (pinfunction "SDO_3") (pintype "passive"))
      (node (ref "D60") (pin "4") (pinfunction "SDI_4") (pintype "passive"))
    )
    (net (code "122") (name "VDD") (class "Default")
      (node (ref "C11") (pin "2") (pinfunction "2_2") (pintype "passive"))
      (node (ref "C12") (pin "2") (pinfunction "2_2") (pintype "passive"))
      (node (ref "C13") (pin "2") (pinfunction "2_2") (pintype "passive"))
      (node (ref "C14") (pin "2") (pinfunction "2_2") (pintype "passive"))
      (node (ref "C16") (pin "2") (pinfunction "2_2") (pintype "passive"))
      (node (ref "C17") (pin "2") (pinfunction "2_2") (pintype "passive"))
      (node (ref "D1") (pin "1") (pinfunction "VDD_1") (pintype "passive"))
      (node (ref "D10") (pin "1") (pinfunction "VDD_1") (pintype "passive"))
      (node (ref "D11") (pin "1") (pinfunction "VDD_1") (pintype "passive"))
      (node (ref "D12") (pin "1") (pinfunction "VDD_1") (pintype "passive"))
      (node (ref "D13") (pin "1") (pinfunction "VDD_1") (pintype "passive"))
      (node (ref "D14") (pin "1") (pinfunction "VDD_1") (pintype "passive"))
      (node (ref "D15") (pin "1") (pinfunction "VDD_1") (pintype "passive"))
      (node (ref "D16") (pin "1") (pinfunction "VDD_1") (pintype "passive"))
      (node (ref "D17") (pin "1") (pinfunction "VDD_1") (pintype "passive"))
      (node (ref "D18") (pin "1") (pinfunction "VDD_1") (pintype "passive"))
      (node (ref "D19") (pin "1") (pinfunction "VDD_1") (pintype "passive"))
      (node (ref "D2") (pin "1") (pinfunction "VDD_1") (pintype "passive"))
      (node (ref "D20") (pin "1") (pinfunction "VDD_1") (pintype "passive"))
      (node (ref "D21") (pin "1") (pinfunction "VDD_1") (pintype "passive"))
      (node (ref "D22") (pin "1") (pinfunction "VDD_1") (pintype "passive"))
      (node (ref "D23") (pin "1") (pinfunction "VDD_1") (pintype "passive"))
      (node (ref "D24") (pin "1") (pinfunction "VDD_1") (pintype "passive"))
      (node (ref "D25") (pin "1") (pinfunction "VDD_1") (pintype "passive"))
      (node (ref "D26") (pin "1") (pinfunction "VDD_1") (pintype "passive"))
      (node (ref "D27") (pin "1") (pinfunction "VDD_1") (pintype "passive"))
      (node (ref "D28") (pin "1") (pinfunction "VDD_1") (pintype "passive"))
      (node (ref "D29") (pin "1") (pinfunction "VDD_1") (pintype "passive"))
      (node (ref "D3") (pin "1") (pinfunction "VDD_1") (pintype "passive"))
      (node (ref "D30") (pin "1") (pinfunction "VDD_1") (pintype "passive"))
      (node (ref "D31") (pin "1") (pinfunction "VDD_1") (pintype "passive"))
      (node (ref "D32") (pin "1") (pinfunction "VDD_1") (pintype "passive"))
      (node (ref "D33") (pin "1") (pinfunction "VDD_1") (pintype "passive"))
      (node (ref "D34") (pin "1") (pinfunction "VDD_1") (pintype "passive"))
      (node (ref "D35") (pin "1") (pinfunction "VDD_1") (pintype "passive"))
      (node (ref "D36") (pin "1") (pinfunction "VDD_1") (pintype "passive"))
      (node (ref "D37") (pin "1") (pinfunction "VDD_1") (pintype "passive"))
      (node (ref "D38") (pin "1") (pinfunction "VDD_1") (pintype "passive"))
      (node (ref "D39") (pin "1") (pinfunction "VDD_1") (pintype "passive"))
      (node (ref "D4") (pin "1") (pinfunction "VDD_1") (pintype "passive"))
      (node (ref "D40") (pin "1") (pinfunction "VDD_1") (pintype "passive"))
      (node (ref "D41") (pin "1") (pinfunction "VDD_1") (pintype "passive"))
      (node (ref "D42") (pin "1") (pinfunction "VDD_1") (pintype "passive"))
      (node (ref "D43") (pin "1") (pinfunction "VDD_1") (pintype "passive"))
      (node (ref "D44") (pin "1") (pinfunction "VDD_1") (pintype "passive"))
      (node (ref "D45") (pin "1") (pinfunction "VDD_1") (pintype "passive"))
      (node (ref "D46") (pin "1") (pinfunction "VDD_1") (pintype "passive"))
      (node (ref "D47") (pin "1") (pinfunction "VDD_1") (pintype "passive"))
      (node (ref "D48") (pin "1") (pinfunction "VDD_1") (pintype "passive"))
      (node (ref "D49") (pin "1") (pinfunction "VDD_1") (pintype "passive"))
      (node (ref "D5") (pin "1") (pinfunction "VDD_1") (pintype "passive"))
      (node (ref "D50") (pin "1") (pinfunction "VDD_1") (pintype "passive"))
      (node (ref "D51") (pin "1") (pinfunction "VDD_1") (pintype "passive"))
      (node (ref "D52") (pin "1") (pinfunction "VDD_1") (pintype "passive"))
      (node (ref "D53") (pin "1") (pinfunction "VDD_1") (pintype "passive"))
      (node (ref "D54") (pin "1") (pinfunction "VDD_1") (pintype "passive"))
      (node (ref "D55") (pin "1") (pinfunction "VDD_1") (pintype "passive"))
      (node (ref "D56") (pin "1") (pinfunction "VDD_1") (pintype "passive"))
      (node (ref "D57") (pin "1") (pinfunction "VDD_1") (pintype "passive"))
      (node (ref "D58") (pin "1") (pinfunction "VDD_1") (pintype "passive"))
      (node (ref "D59") (pin "1") (pinfunction "VDD_1") (pintype "passive"))
      (node (ref "D6") (pin "1") (pinfunction "VDD_1") (pintype "passive"))
      (node (ref "D60") (pin "1") (pinfunction "VDD_1") (pintype "passive"))
      (node (ref "D7") (pin "1") (pinfunction "VDD_1") (pintype "passive"))
      (node (ref "D8") (pin "1") (pinfunction "VDD_1") (pintype "passive"))
      (node (ref "D9") (pin "1") (pinfunction "VDD_1") (pintype "passive"))
    )
    (net (code "123") (name "unconnected-(D60-CKO-Pad2)") (class "Default")
      (node (ref "D60") (pin "2") (pinfunction "CKO_2") (pintype "passive"))
    )
    (net (code "124") (name "unconnected-(D60-SDO-Pad3)") (class "Default")
      (node (ref "D60") (pin "3") (pinfunction "SDO_3") (pintype "passive"))
    )
  )
)
